# TK514_Interrupter.net
KiCad netlist of a schematic drawn in Altium Designer
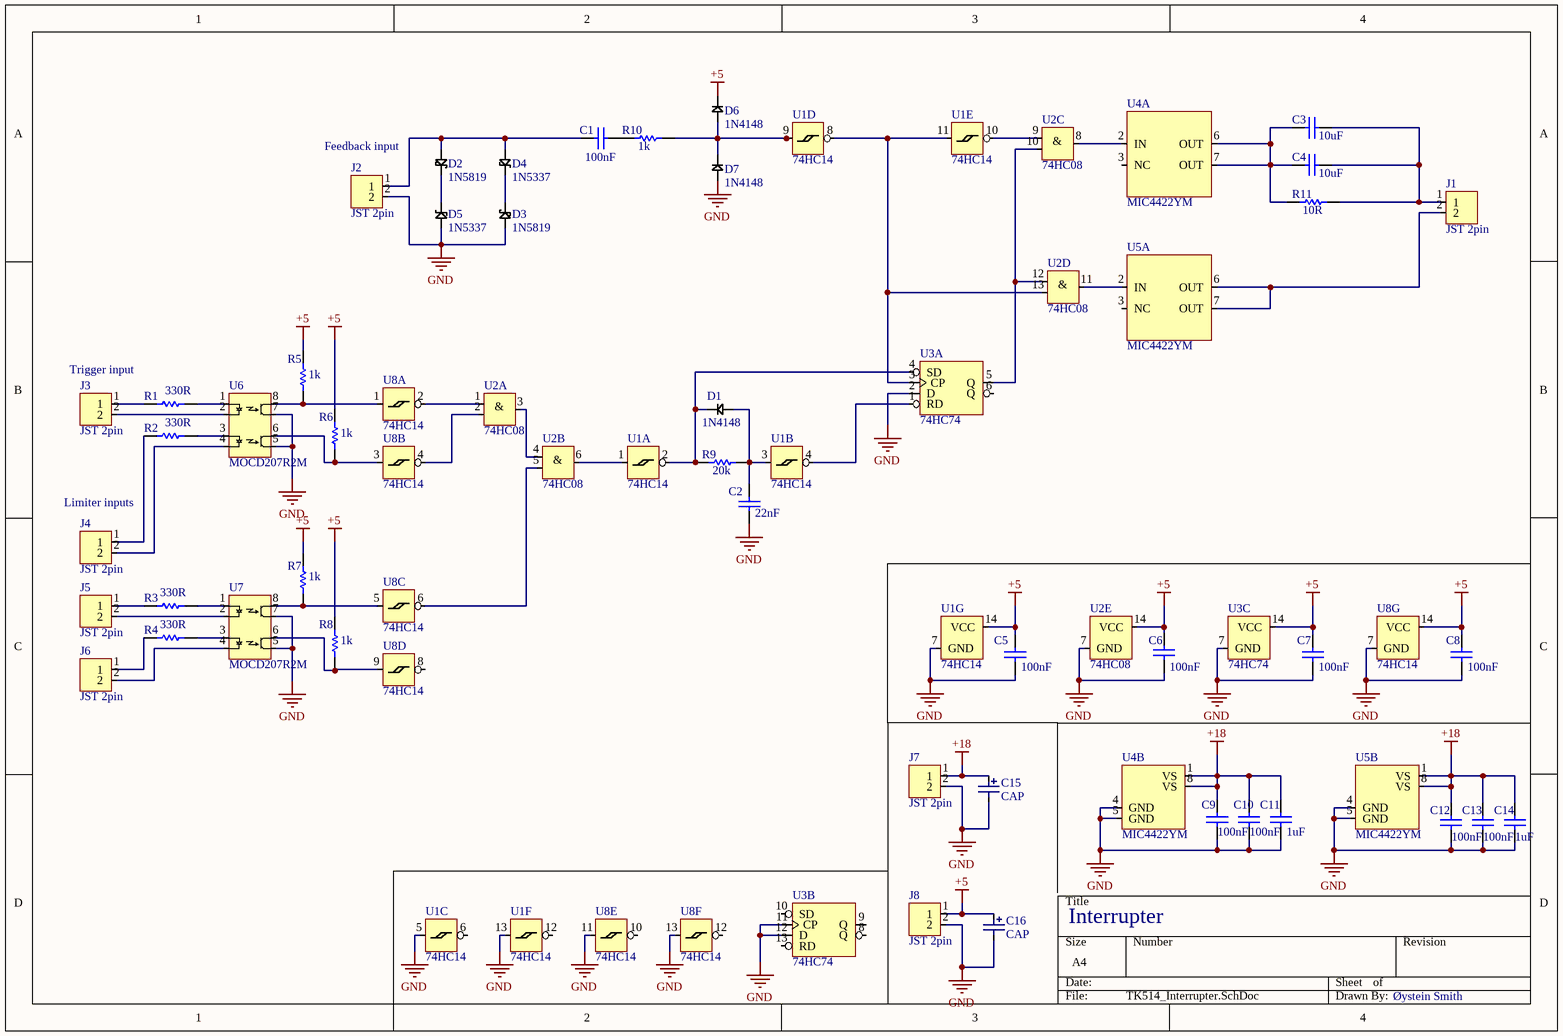
[diagram p0: TK514_Interrupter.SchDoc]

(export (version "E")
  (design (tool "Eeschema 10.0.6"))
  (components
    (comp (ref "C1")
      (value "100nF")
      (footprint "CAPC0805(2012)145_L")
      (description "CAP 100nF 25V ±10% 0805 (2012 Metric) Thickness 1.45mm SMD")
      (fields (field (name "TOLERANCE") "±10%") (field (name "Comment") "CAP 100nF 25V 0805(2012)"))
      (libsource (lib "Altium Content Vault") (part "CMP-1036-04410-1"))
    )
    (comp (ref "C2")
      (value "22nF")
      (footprint "CAPC0805(2012)145_L")
      (description "CAP 22nF 25V ±5% 0805 (2012 Metric) Thickness 1.45mm SMD")
      (fields (field (name "TOLERANCE") "±5%") (field (name "Comment") "CAP 22nF 25V 0805(2012)"))
      (libsource (lib "Altium Content Vault") (part "CMP-1036-04050-1"))
    )
    (comp (ref "C3")
      (value "10uF")
      (footprint "CAPC1206(3216)190_L")
      (description "CAP 10uF 25V ±10% 1206 (3216 Metric) Thickness 1.9mm SMD")
      (fields (field (name "TOLERANCE") "±10%") (field (name "Comment") "CAP 10uF 25V 1206(3216)"))
      (libsource (lib "Altium Content Vault") (part "CMP-1037-04979-1"))
    )
    (comp (ref "C4")
      (value "10uF")
      (footprint "CAPC1206(3216)190_L")
      (description "CAP 10uF 25V ±10% 1206 (3216 Metric) Thickness 1.9mm SMD")
      (fields (field (name "TOLERANCE") "±10%") (field (name "Comment") "CAP 10uF 25V 1206(3216)"))
      (libsource (lib "Altium Content Vault") (part "CMP-1037-04979-1"))
    )
    (comp (ref "C5")
      (value "100nF")
      (footprint "CAPC0805(2012)145_M")
      (description "CAP 100nF 25V ±5% 0805 (2012 Metric) Thickness 1.45mm SMD")
      (fields (field (name "TOLERANCE") "±5%") (field (name "Comment") "CAP 100nF 25V 0805(2012)"))
      (libsource (lib "Altium Content Vault") (part "CMP-1036-04408-1"))
    )
    (comp (ref "C6")
      (value "100nF")
      (footprint "CAPC0805(2012)145_M")
      (description "CAP 100nF 25V ±5% 0805 (2012 Metric) Thickness 1.45mm SMD")
      (fields (field (name "TOLERANCE") "±5%") (field (name "Comment") "CAP 100nF 25V 0805(2012)"))
      (libsource (lib "Altium Content Vault") (part "CMP-1036-04408-1"))
    )
    (comp (ref "C7")
      (value "100nF")
      (footprint "CAPC0805(2012)145_M")
      (description "CAP 100nF 25V ±5% 0805 (2012 Metric) Thickness 1.45mm SMD")
      (fields (field (name "TOLERANCE") "±5%") (field (name "Comment") "CAP 100nF 25V 0805(2012)"))
      (libsource (lib "Altium Content Vault") (part "CMP-1036-04408-1"))
    )
    (comp (ref "C8")
      (value "100nF")
      (footprint "CAPC0805(2012)145_M")
      (description "CAP 100nF 25V ±5% 0805 (2012 Metric) Thickness 1.45mm SMD")
      (fields (field (name "TOLERANCE") "±5%") (field (name "Comment") "CAP 100nF 25V 0805(2012)"))
      (libsource (lib "Altium Content Vault") (part "CMP-1036-04408-1"))
    )
    (comp (ref "C9")
      (value "100nF")
      (footprint "CAPC0805(2012)145_M")
      (description "CAP 100nF 25V ±5% 0805 (2012 Metric) Thickness 1.45mm SMD")
      (fields (field (name "TOLERANCE") "±5%") (field (name "Comment") "CAP 100nF 25V 0805(2012)"))
      (libsource (lib "Altium Content Vault") (part "CMP-1036-04408-1"))
    )
    (comp (ref "C10")
      (value "100nF")
      (footprint "CAPC0805(2012)145_M")
      (description "CAP 100nF 25V ±5% 0805 (2012 Metric) Thickness 1.45mm SMD")
      (fields (field (name "TOLERANCE") "±5%") (field (name "Comment") "CAP 100nF 25V 0805(2012)"))
      (libsource (lib "Altium Content Vault") (part "CMP-1036-04408-1"))
    )
    (comp (ref "C11")
      (value "1uF")
      (footprint "CAPC0805(2012)145_N")
      (description "CAP 1uF 25V ±5% 0805 (2012 Metric) Thickness 1.45mm SMD")
      (fields (field (name "TOLERANCE") "±5%") (field (name "Comment") "CAP 1uF 25V 0805(2012)"))
      (libsource (lib "Altium Content Vault") (part "CMP-1036-04752-1"))
    )
    (comp (ref "C12")
      (value "100nF")
      (footprint "CAPC0805(2012)145_M")
      (description "CAP 100nF 25V ±5% 0805 (2012 Metric) Thickness 1.45mm SMD")
      (fields (field (name "TOLERANCE") "±5%") (field (name "Comment") "CAP 100nF 25V 0805(2012)"))
      (libsource (lib "Altium Content Vault") (part "CMP-1036-04408-1"))
    )
    (comp (ref "C13")
      (value "100nF")
      (footprint "CAPC0805(2012)145_M")
      (description "CAP 100nF 25V ±5% 0805 (2012 Metric) Thickness 1.45mm SMD")
      (fields (field (name "TOLERANCE") "±5%") (field (name "Comment") "CAP 100nF 25V 0805(2012)"))
      (libsource (lib "Altium Content Vault") (part "CMP-1036-04408-1"))
    )
    (comp (ref "C14")
      (value "1uF")
      (footprint "CAPC0805(2012)145_N")
      (description "CAP 1uF 25V ±5% 0805 (2012 Metric) Thickness 1.45mm SMD")
      (fields (field (name "TOLERANCE") "±5%") (field (name "Comment") "CAP 1uF 25V 0805(2012)"))
      (libsource (lib "Altium Content Vault") (part "CMP-1036-04752-1"))
    )
    (comp (ref "C15") (value "CAP") (footprint "CAP 2.5mm") (libsource (lib "Schlib1") (part "CAP")))
    (comp (ref "C16") (value "CAP") (footprint "CAP 2.5mm") (libsource (lib "Schlib1") (part "CAP")))
    (comp (ref "D1") (value "1N4148") (footprint "1N4148") (libsource (lib "Schlib1") (part "1N4148")))
    (comp (ref "D2") (value "1N5819") (footprint "1N5819") (libsource (lib "Schlib1") (part "1N5819")))
    (comp (ref "D3") (value "1N5819") (footprint "1N5819") (libsource (lib "Schlib1") (part "1N5819")))
    (comp (ref "D4") (value "1N5337") (footprint "1N5337") (libsource (lib "Schlib1") (part "1N5337")))
    (comp (ref "D5") (value "1N5337") (footprint "1N5337") (libsource (lib "Schlib1") (part "1N5337")))
    (comp (ref "D6") (value "1N4148") (footprint "1N4148") (libsource (lib "Schlib1") (part "1N4148")))
    (comp (ref "D7") (value "1N4148") (footprint "1N4148") (libsource (lib "Schlib1") (part "1N4148")))
    (comp (ref "J1") (value "JST 2pin") (footprint "JST 2pin") (libsource (lib "") (part "JST 2pin_1")))
    (comp (ref "J2") (value "JST 2pin") (footprint "JST 2pin") (libsource (lib "Schlib1") (part "JST 2pin")))
    (comp (ref "J3") (value "JST 2pin") (footprint "JST 2pin") (libsource (lib "Schlib1") (part "JST 2pin")))
    (comp (ref "J4") (value "JST 2pin") (footprint "JST 2pin") (libsource (lib "Schlib1") (part "JST 2pin")))
    (comp (ref "J5") (value "JST 2pin") (footprint "JST 2pin") (libsource (lib "Schlib1") (part "JST 2pin")))
    (comp (ref "J6") (value "JST 2pin") (footprint "JST 2pin") (libsource (lib "Schlib1") (part "JST 2pin")))
    (comp (ref "J7") (value "JST 2pin") (footprint "JST 2pin") (libsource (lib "Schlib1") (part "JST 2pin")))
    (comp (ref "J8") (value "JST 2pin") (footprint "JST 2pin") (libsource (lib "Schlib1") (part "JST 2pin")))
    (comp (ref "R1")
      (value "330R")
      (footprint "RESC0805(2012)_L")
      (description "330R 0.125W 5% 0805 (2012 Metric)  SMD")
      (fields (field (name "TOLERANCE") "5 %") (field (name "POWER") "0.125 W"))
      (libsource (lib "Altium Content Vault") (part "CMP-1013-00062-1"))
    )
    (comp (ref "R2")
      (value "330R")
      (footprint "RESC0805(2012)_L")
      (description "330R 0.125W 5% 0805 (2012 Metric)  SMD")
      (fields (field (name "TOLERANCE") "5 %") (field (name "POWER") "0.125 W"))
      (libsource (lib "Altium Content Vault") (part "CMP-1013-00062-1"))
    )
    (comp (ref "R3")
      (value "330R")
      (footprint "RESC0805(2012)_L")
      (description "330R 0.125W 5% 0805 (2012 Metric)  SMD")
      (fields (field (name "TOLERANCE") "5 %") (field (name "POWER") "0.125 W"))
      (libsource (lib "Altium Content Vault") (part "CMP-1013-00062-1"))
    )
    (comp (ref "R4")
      (value "330R")
      (footprint "RESC0805(2012)_L")
      (description "330R 0.125W 5% 0805 (2012 Metric)  SMD")
      (fields (field (name "TOLERANCE") "5 %") (field (name "POWER") "0.125 W"))
      (libsource (lib "Altium Content Vault") (part "CMP-1013-00062-1"))
    )
    (comp (ref "R5")
      (value "1k")
      (footprint "RESC0805(2012)_N")
      (description "1K 0.125W 5% 0805 (2012 Metric)  SMD")
      (fields (field (name "POWER") "0.125 W") (field (name "TOLERANCE") "5 %"))
      (libsource (lib "Altium Content Vault") (part "CMP-1013-00074-1"))
    )
    (comp (ref "R6")
      (value "1k")
      (footprint "RESC0805(2012)_N")
      (description "1K 0.125W 5% 0805 (2012 Metric)  SMD")
      (fields (field (name "POWER") "0.125 W") (field (name "TOLERANCE") "5 %"))
      (libsource (lib "Altium Content Vault") (part "CMP-1013-00074-1"))
    )
    (comp (ref "R7")
      (value "1k")
      (footprint "RESC0805(2012)_N")
      (description "1K 0.125W 5% 0805 (2012 Metric)  SMD")
      (fields (field (name "POWER") "0.125 W") (field (name "TOLERANCE") "5 %"))
      (libsource (lib "Altium Content Vault") (part "CMP-1013-00074-1"))
    )
    (comp (ref "R8")
      (value "1k")
      (footprint "RESC0805(2012)_N")
      (description "1K 0.125W 5% 0805 (2012 Metric)  SMD")
      (fields (field (name "POWER") "0.125 W") (field (name "TOLERANCE") "5 %"))
      (libsource (lib "Altium Content Vault") (part "CMP-1013-00074-1"))
    )
    (comp (ref "R9")
      (value "20k")
      (footprint "RESC0805(2012)_N")
      (description "20K 0.125W 1% 0805 (2012 Metric)  SMD")
      (fields (field (name "POWER") "0.125 W") (field (name "TOLERANCE") "1 %"))
      (libsource (lib "Altium Content Vault") (part "CMP-1013-00655-1"))
    )
    (comp (ref "R10")
      (value "1k")
      (footprint "RESC0805(2012)_M")
      (description "1K 0.125W 1% 0805 (2012 Metric)  SMD")
      (fields (field (name "TOLERANCE") "1 %") (field (name "POWER") "0.125 W"))
      (libsource (lib "Altium Content Vault") (part "CMP-1013-00510-1"))
    )
    (comp (ref "R11")
      (value "10R")
      (footprint "RESC0805(2012)_L")
      (description "10R 0.125W 5% 0805 (2012 Metric)  SMD")
      (fields (field (name "POWER") "0.125 W") (field (name "TOLERANCE") "5 %"))
      (libsource (lib "Altium Content Vault") (part "CMP-1013-00026-1"))
    )
    (comp (ref "U1") (value "74HC14") (footprint "SOP14") (libsource (lib "Schlib1") (part "74HC14")))
    (comp (ref "U2") (value "74HC08") (footprint "SOP14") (libsource (lib "Schlib1") (part "74HC08")))
    (comp (ref "U3") (value "74HC74") (footprint "SOP14") (libsource (lib "Schlib1") (part "74HC74")))
    (comp (ref "U4") (value "MIC4422YM") (footprint "SOP8") (libsource (lib "Schlib1") (part "MIC4422YM")))
    (comp (ref "U5") (value "MIC4422YM") (footprint "SOP8") (libsource (lib "Schlib1") (part "MIC4422YM")))
    (comp (ref "U6") (value "MOCD207R2M") (footprint "SOP8") (libsource (lib "Schlib1") (part "MOCD207R2M")))
    (comp (ref "U7") (value "MOCD207R2M") (footprint "SOP8") (libsource (lib "Schlib1") (part "MOCD207R2M")))
    (comp (ref "U8") (value "74HC14") (footprint "SOP14") (libsource (lib "Schlib1") (part "74HC14")))
  )
  (nets
    (net (code "1") (name "+5") (class "Default")
      (node (ref "C16") (pin "2") (pinfunction "2_2") (pintype "passive"))
      (node (ref "C5") (pin "2") (pinfunction "2_2") (pintype "passive"))
      (node (ref "C6") (pin "2") (pinfunction "2_2") (pintype "passive"))
      (node (ref "C7") (pin "2") (pinfunction "2_2") (pintype "passive"))
      (node (ref "C8") (pin "2") (pinfunction "2_2") (pintype "passive"))
      (node (ref "D6") (pin "K") (pinfunction "K_K") (pintype "passive"))
      (node (ref "J8") (pin "1") (pinfunction "1_1") (pintype "passive"))
      (node (ref "R5") (pin "2") (pinfunction "2_2") (pintype "passive"))
      (node (ref "R6") (pin "2") (pinfunction "2_2") (pintype "passive"))
      (node (ref "R7") (pin "2") (pinfunction "2_2") (pintype "passive"))
      (node (ref "R8") (pin "2") (pinfunction "2_2") (pintype "passive"))
      (node (ref "U1") (pin "14") (pinfunction "VCC_14") (pintype "passive"))
      (node (ref "U2") (pin "14") (pinfunction "VCC_14") (pintype "passive"))
      (node (ref "U3") (pin "14") (pinfunction "VCC_14") (pintype "passive"))
      (node (ref "U8") (pin "14") (pinfunction "VCC_14") (pintype "passive"))
    )
    (net (code "2") (name "+18") (class "Default")
      (node (ref "C10") (pin "2") (pinfunction "2_2") (pintype "passive"))
      (node (ref "C11") (pin "2") (pinfunction "2_2") (pintype "passive"))
      (node (ref "C12") (pin "2") (pinfunction "2_2") (pintype "passive"))
      (node (ref "C13") (pin "2") (pinfunction "2_2") (pintype "passive"))
      (node (ref "C14") (pin "2") (pinfunction "2_2") (pintype "passive"))
      (node (ref "C15") (pin "2") (pinfunction "2_2") (pintype "passive"))
      (node (ref "C9") (pin "2") (pinfunction "2_2") (pintype "passive"))
      (node (ref "J7") (pin "1") (pinfunction "1_1") (pintype "passive"))
      (node (ref "U4") (pin "1") (pinfunction "VS_1") (pintype "passive"))
      (node (ref "U4") (pin "8") (pinfunction "VS_8") (pintype "passive"))
      (node (ref "U5") (pin "1") (pinfunction "VS_1") (pintype "passive"))
      (node (ref "U5") (pin "8") (pinfunction "VS_8") (pintype "passive"))
    )
    (net (code "3") (name "GND") (class "Default")
      (node (ref "C10") (pin "1") (pinfunction "1_1") (pintype "passive"))
      (node (ref "C11") (pin "1") (pinfunction "1_1") (pintype "passive"))
      (node (ref "C12") (pin "1") (pinfunction "1_1") (pintype "passive"))
      (node (ref "C13") (pin "1") (pinfunction "1_1") (pintype "passive"))
      (node (ref "C14") (pin "1") (pinfunction "1_1") (pintype "passive"))
      (node (ref "C15") (pin "1") (pinfunction "1_1") (pintype "passive"))
      (node (ref "C16") (pin "1") (pinfunction "1_1") (pintype "passive"))
      (node (ref "C2") (pin "1") (pinfunction "1_1") (pintype "passive"))
      (node (ref "C5") (pin "1") (pinfunction "1_1") (pintype "passive"))
      (node (ref "C6") (pin "1") (pinfunction "1_1") (pintype "passive"))
      (node (ref "C7") (pin "1") (pinfunction "1_1") (pintype "passive"))
      (node (ref "C8") (pin "1") (pinfunction "1_1") (pintype "passive"))
      (node (ref "C9") (pin "1") (pinfunction "1_1") (pintype "passive"))
      (node (ref "D3") (pin "A") (pinfunction "A_A") (pintype "passive"))
      (node (ref "D5") (pin "A") (pinfunction "A_A") (pintype "passive"))
      (node (ref "D7") (pin "A") (pinfunction "A_A") (pintype "passive"))
      (node (ref "J2") (pin "2") (pinfunction "2_2") (pintype "passive"))
      (node (ref "J7") (pin "2") (pinfunction "2_2") (pintype "passive"))
      (node (ref "J8") (pin "2") (pinfunction "2_2") (pintype "passive"))
      (node (ref "U1") (pin "13") (pinfunction "13_13") (pintype "passive"))
      (node (ref "U1") (pin "5") (pinfunction "5_5") (pintype "passive"))
      (node (ref "U1") (pin "7") (pinfunction "GND_7") (pintype "passive"))
      (node (ref "U2") (pin "7") (pinfunction "GND_7") (pintype "passive"))
      (node (ref "U3") (pin "11") (pinfunction "CP_11") (pintype "passive"))
      (node (ref "U3") (pin "12") (pinfunction "D_12") (pintype "passive"))
      (node (ref "U3") (pin "2") (pinfunction "D_2") (pintype "passive"))
      (node (ref "U3") (pin "7") (pinfunction "GND_7") (pintype "passive"))
      (node (ref "U4") (pin "4") (pinfunction "GND_4") (pintype "passive"))
      (node (ref "U4") (pin "5") (pinfunction "GND_5") (pintype "passive"))
      (node (ref "U5") (pin "4") (pinfunction "GND_4") (pintype "passive"))
      (node (ref "U5") (pin "5") (pinfunction "GND_5") (pintype "passive"))
      (node (ref "U6") (pin "5") (pinfunction "5_5") (pintype "passive"))
      (node (ref "U6") (pin "7") (pinfunction "7_7") (pintype "passive"))
      (node (ref "U7") (pin "5") (pinfunction "5_5") (pintype "passive"))
      (node (ref "U7") (pin "7") (pinfunction "7_7") (pintype "passive"))
      (node (ref "U8") (pin "11") (pinfunction "11_11") (pintype "passive"))
      (node (ref "U8") (pin "13") (pinfunction "13_13") (pintype "passive"))
      (node (ref "U8") (pin "7") (pinfunction "GND_7") (pintype "passive"))
    )
    (net (code "4") (name "Net-(C1-Pad1)") (class "Default")
      (node (ref "C1") (pin "1") (pinfunction "1_1") (pintype "passive"))
      (node (ref "D2") (pin "A") (pinfunction "A_A") (pintype "passive"))
      (node (ref "D4") (pin "A") (pinfunction "A_A") (pintype "passive"))
      (node (ref "J2") (pin "1") (pinfunction "1_1") (pintype "passive"))
    )
    (net (code "5") (name "Net-(C1-Pad2)") (class "Default")
      (node (ref "C1") (pin "2") (pinfunction "2_2") (pintype "passive"))
      (node (ref "R10") (pin "1") (pinfunction "1_1") (pintype "passive"))
    )
    (net (code "6") (name "Net-(C2-Pad2)") (class "Default")
      (node (ref "C2") (pin "2") (pinfunction "2_2") (pintype "passive"))
      (node (ref "D1") (pin "A") (pinfunction "A_A") (pintype "passive"))
      (node (ref "R9") (pin "2") (pinfunction "2_2") (pintype "passive"))
      (node (ref "U1") (pin "3") (pinfunction "3_3") (pintype "passive"))
    )
    (net (code "7") (name "Net-(C3-Pad1)") (class "Default")
      (node (ref "C3") (pin "1") (pinfunction "1_1") (pintype "passive"))
      (node (ref "C4") (pin "1") (pinfunction "1_1") (pintype "passive"))
      (node (ref "R11") (pin "1") (pinfunction "1_1") (pintype "passive"))
      (node (ref "U4") (pin "6") (pinfunction "OUT_6") (pintype "passive"))
      (node (ref "U4") (pin "7") (pinfunction "OUT_7") (pintype "passive"))
    )
    (net (code "8") (name "Net-(C3-Pad2)") (class "Default")
      (node (ref "C3") (pin "2") (pinfunction "2_2") (pintype "passive"))
      (node (ref "C4") (pin "2") (pinfunction "2_2") (pintype "passive"))
      (node (ref "J1") (pin "1") (pinfunction "1_1") (pintype "passive"))
      (node (ref "R11") (pin "2") (pinfunction "2_2") (pintype "passive"))
    )
    (net (code "9") (name "Net-(D2-PadK)") (class "Default")
      (node (ref "D2") (pin "K") (pinfunction "K_K") (pintype "passive"))
      (node (ref "D5") (pin "K") (pinfunction "K_K") (pintype "passive"))
    )
    (net (code "10") (name "Net-(D3-PadK)") (class "Default")
      (node (ref "D3") (pin "K") (pinfunction "K_K") (pintype "passive"))
      (node (ref "D4") (pin "K") (pinfunction "K_K") (pintype "passive"))
    )
    (net (code "11") (name "Net-(D6-PadA)") (class "Default")
      (node (ref "D6") (pin "A") (pinfunction "A_A") (pintype "passive"))
      (node (ref "D7") (pin "K") (pinfunction "K_K") (pintype "passive"))
      (node (ref "R10") (pin "2") (pinfunction "2_2") (pintype "passive"))
      (node (ref "U1") (pin "9") (pinfunction "9_9") (pintype "passive"))
    )
    (net (code "12") (name "Net-(J1-Pad2)") (class "Default")
      (node (ref "J1") (pin "2") (pinfunction "2_2") (pintype "passive"))
      (node (ref "U5") (pin "6") (pinfunction "OUT_6") (pintype "passive"))
      (node (ref "U5") (pin "7") (pinfunction "OUT_7") (pintype "passive"))
    )
    (net (code "13") (name "Net-(J3-Pad1)") (class "Default")
      (node (ref "J3") (pin "1") (pinfunction "1_1") (pintype "passive"))
      (node (ref "R1") (pin "2") (pinfunction "2_2") (pintype "passive"))
    )
    (net (code "14") (name "Net-(J3-Pad2)") (class "Default")
      (node (ref "J3") (pin "2") (pinfunction "2_2") (pintype "passive"))
      (node (ref "U6") (pin "2") (pinfunction "2_2") (pintype "passive"))
    )
    (net (code "15") (name "Net-(J4-Pad1)") (class "Default")
      (node (ref "J4") (pin "1") (pinfunction "1_1") (pintype "passive"))
      (node (ref "R2") (pin "2") (pinfunction "2_2") (pintype "passive"))
    )
    (net (code "16") (name "Net-(J4-Pad2)") (class "Default")
      (node (ref "J4") (pin "2") (pinfunction "2_2") (pintype "passive"))
      (node (ref "U6") (pin "4") (pinfunction "4_4") (pintype "passive"))
    )
    (net (code "17") (name "Net-(J5-Pad1)") (class "Default")
      (node (ref "J5") (pin "1") (pinfunction "1_1") (pintype "passive"))
      (node (ref "R3") (pin "2") (pinfunction "2_2") (pintype "passive"))
    )
    (net (code "18") (name "Net-(J5-Pad2)") (class "Default")
      (node (ref "J5") (pin "2") (pinfunction "2_2") (pintype "passive"))
      (node (ref "U7") (pin "2") (pinfunction "2_2") (pintype "passive"))
    )
    (net (code "19") (name "Net-(J6-Pad1)") (class "Default")
      (node (ref "J6") (pin "1") (pinfunction "1_1") (pintype "passive"))
      (node (ref "R4") (pin "2") (pinfunction "2_2") (pintype "passive"))
    )
    (net (code "20") (name "Net-(J6-Pad2)") (class "Default")
      (node (ref "J6") (pin "2") (pinfunction "2_2") (pintype "passive"))
      (node (ref "U7") (pin "4") (pinfunction "4_4") (pintype "passive"))
    )
    (net (code "21") (name "Net-(R1-Pad1)") (class "Default")
      (node (ref "R1") (pin "1") (pinfunction "1_1") (pintype "passive"))
      (node (ref "U6") (pin "1") (pinfunction "1_1") (pintype "passive"))
    )
    (net (code "22") (name "Net-(R2-Pad1)") (class "Default")
      (node (ref "R2") (pin "1") (pinfunction "1_1") (pintype "passive"))
      (node (ref "U6") (pin "3") (pinfunction "3_3") (pintype "passive"))
    )
    (net (code "23") (name "Net-(R3-Pad1)") (class "Default")
      (node (ref "R3") (pin "1") (pinfunction "1_1") (pintype "passive"))
      (node (ref "U7") (pin "1") (pinfunction "1_1") (pintype "passive"))
    )
    (net (code "24") (name "Net-(R4-Pad1)") (class "Default")
      (node (ref "R4") (pin "1") (pinfunction "1_1") (pintype "passive"))
      (node (ref "U7") (pin "3") (pinfunction "3_3") (pintype "passive"))
    )
    (net (code "25") (name "Net-(R5-Pad1)") (class "Default")
      (node (ref "R5") (pin "1") (pinfunction "1_1") (pintype "passive"))
      (node (ref "U6") (pin "8") (pinfunction "8_8") (pintype "passive"))
      (node (ref "U8") (pin "1") (pinfunction "1_1") (pintype "passive"))
    )
    (net (code "26") (name "Net-(R6-Pad1)") (class "Default")
      (node (ref "R6") (pin "1") (pinfunction "1_1") (pintype "passive"))
      (node (ref "U6") (pin "6") (pinfunction "6_6") (pintype "passive"))
      (node (ref "U8") (pin "3") (pinfunction "3_3") (pintype "passive"))
    )
    (net (code "27") (name "Net-(R7-Pad1)") (class "Default")
      (node (ref "R7") (pin "1") (pinfunction "1_1") (pintype "passive"))
      (node (ref "U7") (pin "8") (pinfunction "8_8") (pintype "passive"))
      (node (ref "U8") (pin "5") (pinfunction "5_5") (pintype "passive"))
    )
    (net (code "28") (name "Net-(R8-Pad1)") (class "Default")
      (node (ref "R8") (pin "1") (pinfunction "1_1") (pintype "passive"))
      (node (ref "U7") (pin "6") (pinfunction "6_6") (pintype "passive"))
      (node (ref "U8") (pin "9") (pinfunction "9_9") (pintype "passive"))
    )
    (net (code "29") (name "Net-(U1-Pad1)") (class "Default")
      (node (ref "U1") (pin "1") (pinfunction "1_1") (pintype "passive"))
      (node (ref "U2") (pin "6") (pinfunction "6_6") (pintype "passive"))
    )
    (net (code "30") (name "Net-(U1-Pad10)") (class "Default")
      (node (ref "U1") (pin "10") (pinfunction "10_10") (pintype "passive"))
      (node (ref "U2") (pin "9") (pinfunction "9_9") (pintype "passive"))
    )
    (net (code "31") (name "Net-(U2-Pad1)") (class "Default")
      (node (ref "U2") (pin "1") (pinfunction "1_1") (pintype "passive"))
      (node (ref "U8") (pin "2") (pinfunction "2_2") (pintype "passive"))
    )
    (net (code "32") (name "Net-(U2-Pad2)") (class "Default")
      (node (ref "U2") (pin "2") (pinfunction "2_2") (pintype "passive"))
      (node (ref "U8") (pin "4") (pinfunction "4_4") (pintype "passive"))
    )
    (net (code "33") (name "Net-(U2-Pad3)") (class "Default")
      (node (ref "U2") (pin "3") (pinfunction "3_3") (pintype "passive"))
      (node (ref "U2") (pin "4") (pinfunction "4_4") (pintype "passive"))
    )
    (net (code "34") (name "Net-(U2-Pad5)") (class "Default")
      (node (ref "U2") (pin "5") (pinfunction "5_5") (pintype "passive"))
      (node (ref "U8") (pin "6") (pinfunction "6_6") (pintype "passive"))
    )
    (net (code "35") (name "Net-(U2-Pad10)") (class "Default")
      (node (ref "U2") (pin "10") (pinfunction "10_10") (pintype "passive"))
      (node (ref "U2") (pin "12") (pinfunction "12_12") (pintype "passive"))
      (node (ref "U3") (pin "5") (pinfunction "Q_5") (pintype "passive"))
    )
    (net (code "36") (name "Net-(U3A-CP)") (class "Default")
      (node (ref "U1") (pin "11") (pinfunction "11_11") (pintype "passive"))
      (node (ref "U1") (pin "8") (pinfunction "8_8") (pintype "passive"))
      (node (ref "U2") (pin "13") (pinfunction "13_13") (pintype "passive"))
      (node (ref "U3") (pin "3") (pinfunction "CP_3") (pintype "passive"))
    )
    (net (code "37") (name "Net-(U3A-RD)") (class "Default")
      (node (ref "U1") (pin "4") (pinfunction "4_4") (pintype "passive"))
      (node (ref "U3") (pin "1") (pinfunction "RD_1") (pintype "passive"))
    )
    (net (code "38") (name "Net-(U3A-SD)") (class "Default")
      (node (ref "D1") (pin "K") (pinfunction "K_K") (pintype "passive"))
      (node (ref "R9") (pin "1") (pinfunction "1_1") (pintype "passive"))
      (node (ref "U1") (pin "2") (pinfunction "2_2") (pintype "passive"))
      (node (ref "U3") (pin "4") (pinfunction "SD_4") (pintype "passive"))
    )
    (net (code "39") (name "Net-(U4A-IN)") (class "Default")
      (node (ref "U2") (pin "8") (pinfunction "8_8") (pintype "passive"))
      (node (ref "U4") (pin "2") (pinfunction "IN_2") (pintype "passive"))
    )
    (net (code "40") (name "Net-(U5A-IN)") (class "Default")
      (node (ref "U2") (pin "11") (pinfunction "11_11") (pintype "passive"))
      (node (ref "U5") (pin "2") (pinfunction "IN_2") (pintype "passive"))
    )
    (net (code "41") (name "unconnected-(U1-Pad6)") (class "Default")
      (node (ref "U1") (pin "6") (pinfunction "6_6") (pintype "passive"))
    )
    (net (code "42") (name "unconnected-(U1-Pad12)") (class "Default")
      (node (ref "U1") (pin "12") (pinfunction "12_12") (pintype "passive"))
    )
    (net (code "43") (name "unconnected-(U3A-Q-Pad6)") (class "Default")
      (node (ref "U3") (pin "6") (pinfunction "Q_6") (pintype "passive"))
    )
    (net (code "44") (name "unconnected-(U3B-Q-Pad8)") (class "Default")
      (node (ref "U3") (pin "8") (pinfunction "Q_8") (pintype "passive"))
    )
    (net (code "45") (name "unconnected-(U3B-Q-Pad9)") (class "Default")
      (node (ref "U3") (pin "9") (pinfunction "Q_9") (pintype "passive"))
    )
    (net (code "46") (name "unconnected-(U3B-RD-Pad13)") (class "Default")
      (node (ref "U3") (pin "13") (pinfunction "RD_13") (pintype "passive"))
    )
    (net (code "47") (name "unconnected-(U3B-SD-Pad10)") (class "Default")
      (node (ref "U3") (pin "10") (pinfunction "SD_10") (pintype "passive"))
    )
    (net (code "48") (name "unconnected-(U4A-NC-Pad3)") (class "Default")
      (node (ref "U4") (pin "3") (pinfunction "NC_3") (pintype "passive"))
    )
    (net (code "49") (name "unconnected-(U5A-NC-Pad3)") (class "Default")
      (node (ref "U5") (pin "3") (pinfunction "NC_3") (pintype "passive"))
    )
    (net (code "50") (name "unconnected-(U8-Pad8)") (class "Default")
      (node (ref "U8") (pin "8") (pinfunction "8_8") (pintype "passive"))
    )
    (net (code "51") (name "unconnected-(U8-Pad10)") (class "Default")
      (node (ref "U8") (pin "10") (pinfunction "10_10") (pintype "passive"))
    )
    (net (code "52") (name "unconnected-(U8-Pad12)") (class "Default")
      (node (ref "U8") (pin "12") (pinfunction "12_12") (pintype "passive"))
    )
  )
)
